# LEO_COTS_ant_rev1.net
KiCad netlist of a schematic drawn in Altium Designer
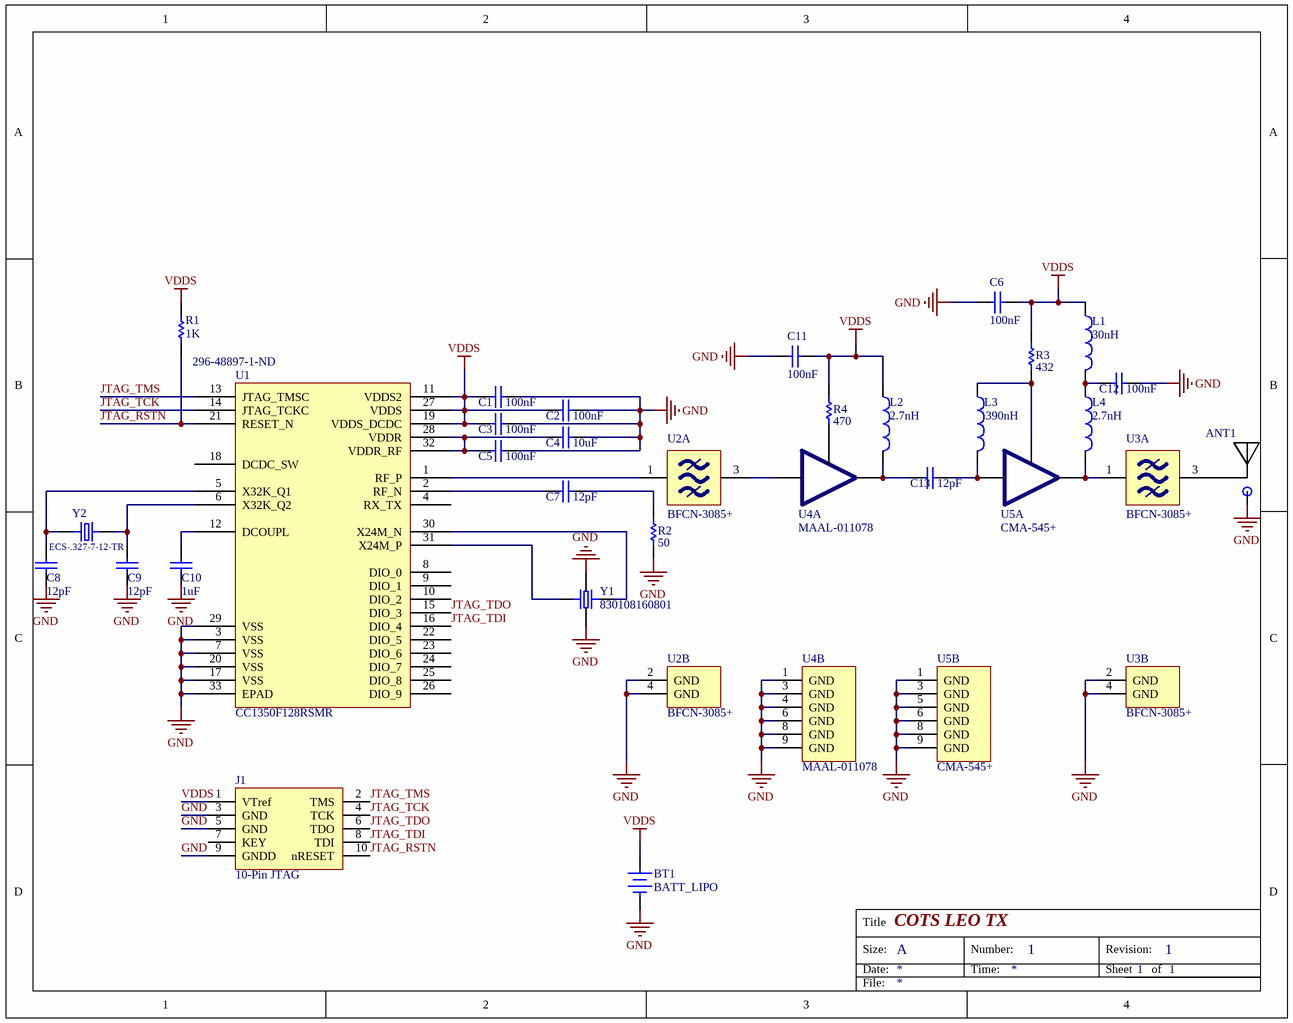
[diagram p0: LEO_COTS_ant_rev1.SchDoc]

(export (version "E")
  (design (tool "Eeschema 10.0.6"))
  (components
    (comp (ref "ANT1")
      (value "ANT")
      (footprint "RESLOOP_OD10_fw15_fl180_sw12_sl15")
      (description "PCB antenna")
      (libsource (lib "LEO_COTS_components") (part "ANT"))
    )
    (comp (ref "BT1")
      (value "BATT_LIPO")
      (footprint "LIPO_1cm_1cm")
      (libsource (lib "LEO_COTS_components") (part "BATT_LIPO"))
    )
    (comp (ref "C1")
      (value "100nF")
      (footprint "CAPC0603X04N")
      (description "CAP CER 100nF 0201")
      (fields (field (name "Comment") "CAP_0201"))
      (libsource (lib "LEO_COTS_components") (part "CAP_0201"))
    )
    (comp (ref "C2")
      (value "100nF")
      (footprint "CAPC0603X04N")
      (description "CAP CER 100nF 0201")
      (fields (field (name "Comment") "CAP_0201"))
      (libsource (lib "LEO_COTS_components") (part "CAP_0201"))
    )
    (comp (ref "C3")
      (value "100nF")
      (footprint "CAPC0603X04N")
      (description "CAP CER 100nF 0201")
      (fields (field (name "Comment") "CAP_0201"))
      (libsource (lib "LEO_COTS_components") (part "CAP_0201"))
    )
    (comp (ref "C4")
      (value "10uF")
      (footprint "CAPC1608X05N")
      (description "CAP CER 10uF 0603")
      (fields (field (name "Comment") "CAP_0603"))
      (libsource (lib "LEO_COTS_components") (part "CAP_0603"))
    )
    (comp (ref "C5")
      (value "100nF")
      (footprint "CAPC0603X04N")
      (description "CAP CER 100nF 0201")
      (fields (field (name "Comment") "CAP_0201"))
      (libsource (lib "LEO_COTS_components") (part "CAP_0201"))
    )
    (comp (ref "C6")
      (value "100nF")
      (footprint "CAPC0603X04N")
      (description "CAP CER 100nF 0201")
      (fields (field (name "Comment") "CAP_0201"))
      (libsource (lib "LEO_COTS_components") (part "CAP_0201"))
    )
    (comp (ref "C7")
      (value "12pF")
      (footprint "CAPC0603X04N")
      (description "CAP CER 12pF 0201")
      (fields (field (name "Comment") "CAP_0201"))
      (libsource (lib "LEO_COTS_components") (part "CAP_0201"))
    )
    (comp (ref "C8")
      (value "12pF")
      (footprint "CAPC0603X04N")
      (description "CAP CER 12pF 0201")
      (fields (field (name "Comment") "CAP_0201"))
      (libsource (lib "LEO_COTS_components") (part "CAP_0201"))
    )
    (comp (ref "C9")
      (value "12pF")
      (footprint "CAPC0603X04N")
      (description "CAP CER 12pF 0201")
      (fields (field (name "Comment") "CAP_0201"))
      (libsource (lib "LEO_COTS_components") (part "CAP_0201"))
    )
    (comp (ref "C10")
      (value "1uF")
      (footprint "CAPC0603X04N")
      (description "CAP CER 1uF 0201")
      (fields (field (name "Comment") "CAP_0201"))
      (libsource (lib "LEO_COTS_components") (part "CAP_0201"))
    )
    (comp (ref "C11")
      (value "100nF")
      (footprint "CAPC0603X04N")
      (description "CAP CER 100nF 0201")
      (fields (field (name "Comment") "CAP_0201"))
      (libsource (lib "LEO_COTS_components") (part "CAP_0201"))
    )
    (comp (ref "C12")
      (value "100nF")
      (footprint "CAPC0603X04N")
      (description "CAP CER 100nF 0201")
      (fields (field (name "Comment") "CAP_0201"))
      (libsource (lib "LEO_COTS_components") (part "CAP_0201"))
    )
    (comp (ref "C13")
      (value "12pF")
      (footprint "CAPC0603X04N")
      (description "CAP CER 12pF 0201")
      (fields (field (name "Comment") "CAP_0201"))
      (libsource (lib "LEO_COTS_components") (part "CAP_0201"))
    )
    (comp (ref "J1")
      (value "10-Pin JTAG")
      (footprint "FTSH-105-01-F-DV-007-K")
      (description "10-pin JTAG")
      (libsource (lib "LEO_COTS_components") (part "CM10"))
    )
    (comp (ref "L1")
      (value "30nH")
      (footprint "0402")
      (description "Inductor")
      (fields (field (name "PUBLISHER") "Altium Limited"))
      (libsource (lib "LEO_COTS_components") (part "Inductor"))
    )
    (comp (ref "L2")
      (value "2.7nH")
      (footprint "0402")
      (description "Inductor")
      (fields (field (name "PUBLISHER") "Altium Limited"))
      (libsource (lib "LEO_COTS_components") (part "Inductor"))
    )
    (comp (ref "L3")
      (value "390nH")
      (footprint "1608[0603]")
      (description "Inductor")
      (fields (field (name "PUBLISHER") "Altium Limited"))
      (libsource (lib "LEO_COTS_components") (part "Inductor"))
    )
    (comp (ref "L4")
      (value "2.7nH")
      (footprint "0402")
      (description "Inductor")
      (fields (field (name "PUBLISHER") "Altium Limited"))
      (libsource (lib "LEO_COTS_components") (part "Inductor"))
    )
    (comp (ref "R1")
      (value "1K")
      (footprint "CAPC0603X04N")
      (description "RES 1K OHM 0201")
      (fields (field (name "Comment") "RES_0201") (field (name "PUBLISHER") "Altium Limited"))
      (libsource (lib "LEO_COTS_components") (part "Res Semi"))
    )
    (comp (ref "R2")
      (value "50")
      (footprint "CAPC0603X04N")
      (description "RES 50 OHM 0201")
      (fields (field (name "Comment") "RES_0201") (field (name "PUBLISHER") "Altium Limited"))
      (libsource (lib "LEO_COTS_components") (part "Res Semi"))
    )
    (comp (ref "R3")
      (value "432")
      (footprint "CAPC0603X04N")
      (description "RES 50 OHM 0201")
      (fields (field (name "Comment") "RES_0201") (field (name "PUBLISHER") "Altium Limited"))
      (libsource (lib "LEO_COTS_components") (part "Res Semi"))
    )
    (comp (ref "R4")
      (value "470")
      (footprint "CAPC0603X04N")
      (description "RES 50 OHM 0201")
      (fields (field (name "Comment") "RES_0201") (field (name "PUBLISHER") "Altium Limited"))
      (libsource (lib "LEO_COTS_components") (part "Res Semi"))
    )
    (comp (ref "U1")
      (value "CC1350F128RSMR")
      (footprint "QFN40P400X400X100-33N")
      (description "Ultra-Low-Power Dual-Band Wireless MCU")
      (fields (field (name "SUPPLIER PART NUMBER 1") "296-48897-1-ND"))
      (libsource (lib "LEO_COTS_components") (part "CC1350F128RSMR"))
    )
    (comp (ref "U2")
      (value "BFCN-3085+")
      (footprint "FV1206")
      (description "2800 to 3400 MHz Band-Pass Filter")
      (libsource (lib "LEO_COTS_components") (part "BFCN-3085+"))
    )
    (comp (ref "U3")
      (value "BFCN-3085+")
      (footprint "FV1206")
      (description "2800 to 3400 MHz Band-Pass Filter")
      (libsource (lib "LEO_COTS_components") (part "BFCN-3085+"))
    )
    (comp (ref "U4")
      (value "MAAL-011078")
      (footprint "PDFN-8")
      (description "Wideband LNA")
      (libsource (lib "LEO_COTS_components") (part "MAAL-011078"))
    )
    (comp (ref "U5")
      (value "CMA-545+")
      (footprint "DL1721")
      (description "Wideband LNA")
      (libsource (lib "LEO_COTS_components") (part "CMA-545+"))
    )
    (comp (ref "Y1")
      (value "830108160801")
      (footprint "LFXTAL081608")
      (description "24 MHz crystal")
      (fields (field (name "MP") "ECS-.327-7-12-TR"))
      (libsource (lib "LEO_COTS_components") (part "830108160801"))
    )
    (comp (ref "Y2")
      (value "ECS-.327-7-12-TR")
      (footprint "XTAL_ECS-.327-7-12-TR")
      (description "32.768 kHz SMD Crystal")
      (libsource (lib "LEO_COTS_components") (part "ECS-.327-7-12-TR"))
    )
  )
  (nets
    (net (code "1") (name "/JTAG_RSTN") (class "Default")
      (node (ref "J1") (pin "10") (pinfunction "nRESET_10") (pintype "passive"))
      (node (ref "R1") (pin "1") (pinfunction "1_1") (pintype "passive"))
      (node (ref "U1") (pin "21") (pinfunction "RESET_N_21") (pintype "passive"))
    )
    (net (code "2") (name "/JTAG_TCK") (class "Default")
      (node (ref "J1") (pin "4") (pinfunction "TCK_4") (pintype "passive"))
      (node (ref "U1") (pin "14") (pinfunction "JTAG_TCKC_14") (pintype "passive"))
    )
    (net (code "3") (name "/JTAG_TDI") (class "Default")
      (node (ref "J1") (pin "8") (pinfunction "TDI_8") (pintype "passive"))
      (node (ref "U1") (pin "16") (pinfunction "DIO_4_16") (pintype "passive"))
    )
    (net (code "4") (name "/JTAG_TDO") (class "Default")
      (node (ref "J1") (pin "6") (pinfunction "TDO_6") (pintype "passive"))
      (node (ref "U1") (pin "15") (pinfunction "DIO_3_15") (pintype "passive"))
    )
    (net (code "5") (name "/JTAG_TMS") (class "Default")
      (node (ref "J1") (pin "2") (pinfunction "TMS_2") (pintype "passive"))
      (node (ref "U1") (pin "13") (pinfunction "JTAG_TMSC_13") (pintype "passive"))
    )
    (net (code "6") (name "GND") (class "Default")
      (node (ref "ANT1") (pin "2") (pinfunction "-_2") (pintype "passive"))
      (node (ref "BT1") (pin "2") (pinfunction "-_2") (pintype "passive"))
      (node (ref "C1") (pin "1") (pinfunction "1_1") (pintype "passive"))
      (node (ref "C10") (pin "1") (pinfunction "1_1") (pintype "passive"))
      (node (ref "C11") (pin "1") (pinfunction "1_1") (pintype "passive"))
      (node (ref "C12") (pin "1") (pinfunction "1_1") (pintype "passive"))
      (node (ref "C2") (pin "1") (pinfunction "1_1") (pintype "passive"))
      (node (ref "C3") (pin "1") (pinfunction "1_1") (pintype "passive"))
      (node (ref "C4") (pin "2") (pinfunction "2_2") (pintype "passive"))
      (node (ref "C5") (pin "1") (pinfunction "1_1") (pintype "passive"))
      (node (ref "C6") (pin "1") (pinfunction "1_1") (pintype "passive"))
      (node (ref "C8") (pin "1") (pinfunction "1_1") (pintype "passive"))
      (node (ref "C9") (pin "1") (pinfunction "1_1") (pintype "passive"))
      (node (ref "J1") (pin "3") (pinfunction "GND_3") (pintype "passive"))
      (node (ref "J1") (pin "5") (pinfunction "GND_5") (pintype "passive"))
      (node (ref "J1") (pin "9") (pinfunction "GNDD_9") (pintype "passive"))
      (node (ref "R2") (pin "1") (pinfunction "1_1") (pintype "passive"))
      (node (ref "U1") (pin "17") (pinfunction "VSS_17") (pintype "passive"))
      (node (ref "U1") (pin "20") (pinfunction "VSS_20") (pintype "passive"))
      (node (ref "U1") (pin "29") (pinfunction "VSS_29") (pintype "passive"))
      (node (ref "U1") (pin "3") (pinfunction "VSS_3") (pintype "passive"))
      (node (ref "U1") (pin "33") (pinfunction "EPAD_33") (pintype "passive"))
      (node (ref "U1") (pin "7") (pinfunction "VSS_7") (pintype "passive"))
      (node (ref "U2") (pin "2") (pinfunction "GND_2") (pintype "tri_state"))
      (node (ref "U2") (pin "4") (pinfunction "GND_4") (pintype "tri_state"))
      (node (ref "U3") (pin "2") (pinfunction "GND_2") (pintype "tri_state"))
      (node (ref "U3") (pin "4") (pinfunction "GND_4") (pintype "tri_state"))
      (node (ref "U4") (pin "1") (pinfunction "GND_1") (pintype "tri_state"))
      (node (ref "U4") (pin "3") (pinfunction "GND_3") (pintype "tri_state"))
      (node (ref "U4") (pin "4") (pinfunction "GND_4") (pintype "tri_state"))
      (node (ref "U4") (pin "6") (pinfunction "GND_6") (pintype "tri_state"))
      (node (ref "U4") (pin "8") (pinfunction "GND_8") (pintype "tri_state"))
      (node (ref "U4") (pin "9") (pinfunction "GND_9") (pintype "tri_state"))
      (node (ref "U5") (pin "1") (pinfunction "GND_1") (pintype "tri_state"))
      (node (ref "U5") (pin "3") (pinfunction "GND_3") (pintype "tri_state"))
      (node (ref "U5") (pin "5") (pinfunction "GND_5") (pintype "tri_state"))
      (node (ref "U5") (pin "6") (pinfunction "GND_6") (pintype "tri_state"))
      (node (ref "U5") (pin "8") (pinfunction "GND_8") (pintype "tri_state"))
      (node (ref "U5") (pin "9") (pinfunction "GND_9") (pintype "tri_state"))
      (node (ref "Y1") (pin "2") (pinfunction "2_2") (pintype "passive"))
      (node (ref "Y1") (pin "4") (pinfunction "4_4") (pintype "passive"))
    )
    (net (code "7") (name "Net-(ANT1-+)") (class "Default")
      (node (ref "ANT1") (pin "1") (pinfunction "+_1") (pintype "passive"))
      (node (ref "U3") (pin "3") (pinfunction "OUT_3") (pintype "tri_state"))
    )
    (net (code "8") (name "Net-(C7-Pad1)") (class "Default")
      (node (ref "C7") (pin "1") (pinfunction "1_1") (pintype "passive"))
      (node (ref "R2") (pin "2") (pinfunction "2_2") (pintype "passive"))
    )
    (net (code "9") (name "Net-(C12-Pad2)") (class "Default")
      (node (ref "C12") (pin "2") (pinfunction "2_2") (pintype "passive"))
      (node (ref "L1") (pin "2") (pinfunction "2_2") (pintype "passive"))
      (node (ref "L4") (pin "1") (pinfunction "1_1") (pintype "passive"))
    )
    (net (code "10") (name "Net-(U1-DCOUPL)") (class "Default")
      (node (ref "C10") (pin "2") (pinfunction "2_2") (pintype "passive"))
      (node (ref "U1") (pin "12") (pinfunction "DCOUPL_12") (pintype "passive"))
    )
    (net (code "11") (name "Net-(U1-RF_N)") (class "Default")
      (node (ref "C7") (pin "2") (pinfunction "2_2") (pintype "passive"))
      (node (ref "U1") (pin "2") (pinfunction "RF_N_2") (pintype "passive"))
    )
    (net (code "12") (name "Net-(U1-RF_P)") (class "Default")
      (node (ref "U1") (pin "1") (pinfunction "RF_P_1") (pintype "passive"))
      (node (ref "U2") (pin "1") (pinfunction "IN_1") (pintype "tri_state"))
    )
    (net (code "13") (name "Net-(U1-VDDR)") (class "Default")
      (node (ref "C4") (pin "1") (pinfunction "1_1") (pintype "passive"))
      (node (ref "C5") (pin "2") (pinfunction "2_2") (pintype "passive"))
      (node (ref "U1") (pin "28") (pinfunction "VDDR_28") (pintype "passive"))
      (node (ref "U1") (pin "32") (pinfunction "VDDR_RF_32") (pintype "passive"))
    )
    (net (code "14") (name "Net-(U1-X24M_N)") (class "Default")
      (node (ref "U1") (pin "30") (pinfunction "X24M_N_30") (pintype "passive"))
      (node (ref "Y1") (pin "3") (pinfunction "3_3") (pintype "passive"))
    )
    (net (code "15") (name "Net-(U1-X24M_P)") (class "Default")
      (node (ref "U1") (pin "31") (pinfunction "X24M_P_31") (pintype "passive"))
      (node (ref "Y1") (pin "1") (pinfunction "1_1") (pintype "passive"))
    )
    (net (code "16") (name "Net-(U1-X32K_Q1)") (class "Default")
      (node (ref "C8") (pin "2") (pinfunction "2_2") (pintype "passive"))
      (node (ref "U1") (pin "5") (pinfunction "X32K_Q1_5") (pintype "passive"))
      (node (ref "Y2") (pin "1") (pinfunction "1_1") (pintype "passive"))
    )
    (net (code "17") (name "Net-(U1-X32K_Q2)") (class "Default")
      (node (ref "C9") (pin "2") (pinfunction "2_2") (pintype "passive"))
      (node (ref "U1") (pin "6") (pinfunction "X32K_Q2_6") (pintype "passive"))
      (node (ref "Y2") (pin "2") (pinfunction "2_2") (pintype "passive"))
    )
    (net (code "18") (name "Net-(U2A-OUT)") (class "Default")
      (node (ref "U2") (pin "3") (pinfunction "OUT_3") (pintype "tri_state"))
      (node (ref "U4") (pin "2") (pinfunction "IN_2") (pintype "tri_state"))
    )
    (net (code "19") (name "Net-(U3A-IN)") (class "Default")
      (node (ref "L4") (pin "2") (pinfunction "2_2") (pintype "passive"))
      (node (ref "U3") (pin "1") (pinfunction "IN_1") (pintype "tri_state"))
      (node (ref "U5") (pin "7") (pinfunction "OUT_7") (pintype "tri_state"))
    )
    (net (code "20") (name "Net-(U4A-BIAS)") (class "Default")
      (node (ref "R4") (pin "1") (pinfunction "1_1") (pintype "passive"))
      (node (ref "U4") (pin "5") (pinfunction "BIAS_5") (pintype "tri_state"))
    )
    (net (code "21") (name "Net-(U4A-OUT)") (class "Default")
      (node (ref "C13") (pin "2") (pinfunction "2_2") (pintype "passive"))
      (node (ref "L2") (pin "2") (pinfunction "2_2") (pintype "passive"))
      (node (ref "U4") (pin "7") (pinfunction "OUT_7") (pintype "tri_state"))
    )
    (net (code "22") (name "Net-(U5A-BIAS)") (class "Default")
      (node (ref "L3") (pin "1") (pinfunction "1_1") (pintype "passive"))
      (node (ref "R3") (pin "1") (pinfunction "1_1") (pintype "passive"))
      (node (ref "U5") (pin "4") (pinfunction "BIAS_4") (pintype "tri_state"))
    )
    (net (code "23") (name "Net-(U5A-IN)") (class "Default")
      (node (ref "C13") (pin "1") (pinfunction "1_1") (pintype "passive"))
      (node (ref "L3") (pin "2") (pinfunction "2_2") (pintype "passive"))
      (node (ref "U5") (pin "2") (pinfunction "IN_2") (pintype "tri_state"))
    )
    (net (code "24") (name "VDDS") (class "Default")
      (node (ref "BT1") (pin "1") (pinfunction "+_1") (pintype "passive"))
      (node (ref "C1") (pin "2") (pinfunction "2_2") (pintype "passive"))
      (node (ref "C11") (pin "2") (pinfunction "2_2") (pintype "passive"))
      (node (ref "C2") (pin "2") (pinfunction "2_2") (pintype "passive"))
      (node (ref "C3") (pin "2") (pinfunction "2_2") (pintype "passive"))
      (node (ref "C6") (pin "2") (pinfunction "2_2") (pintype "passive"))
      (node (ref "J1") (pin "1") (pinfunction "VTref_1") (pintype "passive"))
      (node (ref "L1") (pin "1") (pinfunction "1_1") (pintype "passive"))
      (node (ref "L2") (pin "1") (pinfunction "1_1") (pintype "passive"))
      (node (ref "R1") (pin "2") (pinfunction "2_2") (pintype "passive"))
      (node (ref "R3") (pin "2") (pinfunction "2_2") (pintype "passive"))
      (node (ref "R4") (pin "2") (pinfunction "2_2") (pintype "passive"))
      (node (ref "U1") (pin "11") (pinfunction "VDDS2_11") (pintype "passive"))
      (node (ref "U1") (pin "19") (pinfunction "VDDS_DCDC_19") (pintype "passive"))
      (node (ref "U1") (pin "27") (pinfunction "VDDS_27") (pintype "passive"))
    )
    (net (code "25") (name "unconnected-(J1-KEY-Pad7)") (class "Default")
      (node (ref "J1") (pin "7") (pinfunction "KEY_7") (pintype "passive"))
    )
    (net (code "26") (name "unconnected-(U1-DCDC_SW-Pad18)") (class "Default")
      (node (ref "U1") (pin "18") (pinfunction "DCDC_SW_18") (pintype "passive"))
    )
    (net (code "27") (name "unconnected-(U1-DIO_0-Pad8)") (class "Default")
      (node (ref "U1") (pin "8") (pinfunction "DIO_0_8") (pintype "passive"))
    )
    (net (code "28") (name "unconnected-(U1-DIO_1-Pad9)") (class "Default")
      (node (ref "U1") (pin "9") (pinfunction "DIO_1_9") (pintype "passive"))
    )
    (net (code "29") (name "unconnected-(U1-DIO_2-Pad10)") (class "Default")
      (node (ref "U1") (pin "10") (pinfunction "DIO_2_10") (pintype "passive"))
    )
    (net (code "30") (name "unconnected-(U1-DIO_5-Pad22)") (class "Default")
      (node (ref "U1") (pin "22") (pinfunction "DIO_5_22") (pintype "passive"))
    )
    (net (code "31") (name "unconnected-(U1-DIO_6-Pad23)") (class "Default")
      (node (ref "U1") (pin "23") (pinfunction "DIO_6_23") (pintype "passive"))
    )
    (net (code "32") (name "unconnected-(U1-DIO_7-Pad24)") (class "Default")
      (node (ref "U1") (pin "24") (pinfunction "DIO_7_24") (pintype "passive"))
    )
    (net (code "33") (name "unconnected-(U1-DIO_8-Pad25)") (class "Default")
      (node (ref "U1") (pin "25") (pinfunction "DIO_8_25") (pintype "passive"))
    )
    (net (code "34") (name "unconnected-(U1-DIO_9-Pad26)") (class "Default")
      (node (ref "U1") (pin "26") (pinfunction "DIO_9_26") (pintype "passive"))
    )
    (net (code "35") (name "unconnected-(U1-RX_TX-Pad4)") (class "Default")
      (node (ref "U1") (pin "4") (pinfunction "RX_TX_4") (pintype "passive"))
    )
  )
)
